# Steering_Daughterboard.net
KiCad netlist of a schematic drawn in Altium Designer
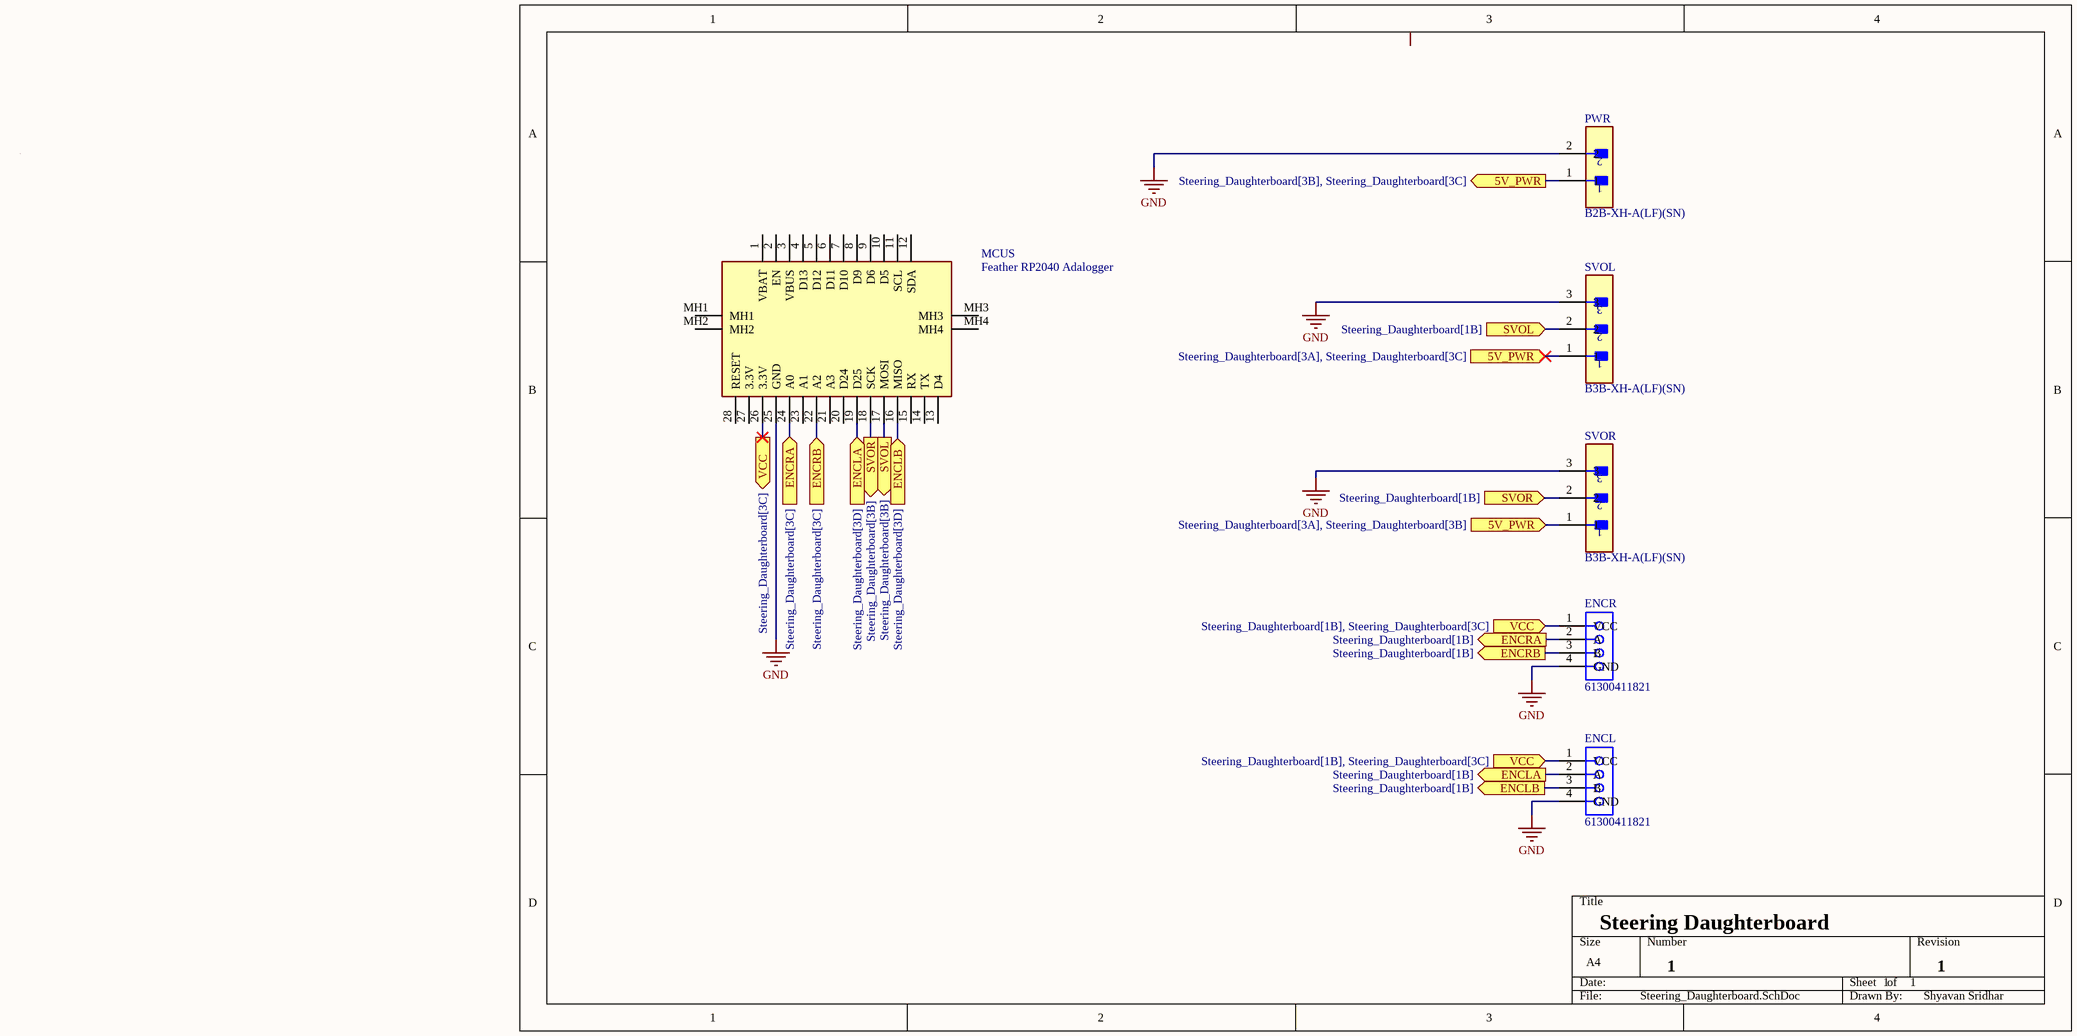
[diagram p0: Steering_Daughterboard.SchDoc]

(export (version "E")
  (design (tool "Eeschema 10.0.6"))
  (components
    (comp (ref "ENCL")
      (value "61300411821")
      (footprint "61300411821")
      (libsource (lib "Altium Content Vault") (part "Header_Female_1R_04P"))
    )
    (comp (ref "ENCR")
      (value "61300411821")
      (footprint "61300411821")
      (libsource (lib "Altium Content Vault") (part "Header_Female_1R_04P"))
    )
    (comp (ref "MCUS")
      (value "Feather RP2040 Adalogger")
      (footprint "SamacSys:2796")
      (description "Adafruit Microcontroller")
      (fields (field (name "MANUFACTURER_PART_NUMBER") "4884") (field (name "MOUSER PART NUMBER") "485-5980"))
      (libsource (lib "*") (part "2796"))
    )
    (comp (ref "PWR")
      (value "B2B-XH-A(LF)(SN)")
      (footprint "FP-B2B-XH-A_LF_SN-MFG")
      (description "CONN HEADER VERT 2POS 2.5MM")
      (libsource (lib "Altium Content Vault") (part "3bc925449376181038e59eaffc5286c"))
    )
    (comp (ref "SVOL")
      (value "B3B-XH-A(LF)(SN)")
      (footprint "FP-B3B-XH-A_LF_SN-MFG")
      (description "CONN HEADER VERT 3POS 2.5MM")
      (libsource (lib "Altium Content Vault") (part "0d3f023dd272f625e17a2be33dea85f"))
    )
    (comp (ref "SVOR")
      (value "B3B-XH-A(LF)(SN)")
      (footprint "FP-B3B-XH-A_LF_SN-MFG")
      (description "CONN HEADER VERT 3POS 2.5MM")
      (libsource (lib "Altium Content Vault") (part "0d3f023dd272f625e17a2be33dea85f"))
    )
  )
  (nets
    (net (code "1") (name "/5V_PWR") (class "Default")
      (node (ref "PWR") (pin "1") (pinfunction "1_1") (pintype "passive"))
      (node (ref "SVOL") (pin "1") (pinfunction "1_1") (pintype "passive"))
      (node (ref "SVOR") (pin "1") (pinfunction "1_1") (pintype "passive"))
    )
    (net (code "2") (name "/ENCLA") (class "Default")
      (node (ref "ENCL") (pin "2") (pinfunction "A_2") (pintype "passive"))
      (node (ref "MCUS") (pin "19") (pinfunction "D25_19") (pintype "passive"))
    )
    (net (code "3") (name "/ENCLB") (class "Default")
      (node (ref "ENCL") (pin "3") (pinfunction "B_3") (pintype "passive"))
      (node (ref "MCUS") (pin "16") (pinfunction "MISO_16") (pintype "passive"))
    )
    (net (code "4") (name "/ENCRA") (class "Default")
      (node (ref "ENCR") (pin "2") (pinfunction "A_2") (pintype "passive"))
      (node (ref "MCUS") (pin "24") (pinfunction "A0_24") (pintype "passive"))
    )
    (net (code "5") (name "/ENCRB") (class "Default")
      (node (ref "ENCR") (pin "3") (pinfunction "B_3") (pintype "passive"))
      (node (ref "MCUS") (pin "22") (pinfunction "A2_22") (pintype "passive"))
    )
    (net (code "6") (name "/SVOL") (class "Default")
      (node (ref "MCUS") (pin "17") (pinfunction "MOSI_17") (pintype "passive"))
      (node (ref "SVOL") (pin "2") (pinfunction "2_2") (pintype "passive"))
    )
    (net (code "7") (name "/SVOR") (class "Default")
      (node (ref "MCUS") (pin "18") (pinfunction "SCK_18") (pintype "passive"))
      (node (ref "SVOR") (pin "2") (pinfunction "2_2") (pintype "passive"))
    )
    (net (code "8") (name "/VCC") (class "Default")
      (node (ref "ENCL") (pin "1") (pinfunction "VCC_1") (pintype "passive"))
      (node (ref "ENCR") (pin "1") (pinfunction "VCC_1") (pintype "passive"))
      (node (ref "MCUS") (pin "26") (pinfunction "3.3V_26") (pintype "passive"))
    )
    (net (code "9") (name "GND") (class "Default")
      (node (ref "ENCL") (pin "4") (pinfunction "GND_4") (pintype "passive"))
      (node (ref "ENCR") (pin "4") (pinfunction "GND_4") (pintype "passive"))
      (node (ref "MCUS") (pin "25") (pinfunction "GND_25") (pintype "passive"))
      (node (ref "PWR") (pin "2") (pinfunction "2_2") (pintype "passive"))
      (node (ref "SVOL") (pin "3") (pinfunction "3_3") (pintype "passive"))
      (node (ref "SVOR") (pin "3") (pinfunction "3_3") (pintype "passive"))
    )
    (net (code "10") (name "unconnected-(MCUS-3.3V-Pad27)") (class "Default")
      (node (ref "MCUS") (pin "27") (pinfunction "3.3V_27") (pintype "passive"))
    )
    (net (code "11") (name "unconnected-(MCUS-A1-Pad23)") (class "Default")
      (node (ref "MCUS") (pin "23") (pinfunction "A1_23") (pintype "passive"))
    )
    (net (code "12") (name "unconnected-(MCUS-A3-Pad21)") (class "Default")
      (node (ref "MCUS") (pin "21") (pinfunction "A3_21") (pintype "passive"))
    )
    (net (code "13") (name "unconnected-(MCUS-D4-Pad13)") (class "Default")
      (node (ref "MCUS") (pin "13") (pinfunction "D4_13") (pintype "passive"))
    )
    (net (code "14") (name "unconnected-(MCUS-D5-Pad10)") (class "Default")
      (node (ref "MCUS") (pin "10") (pinfunction "D5_10") (pintype "passive"))
    )
    (net (code "15") (name "unconnected-(MCUS-D6-Pad9)") (class "Default")
      (node (ref "MCUS") (pin "9") (pinfunction "D6_9") (pintype "passive"))
    )
    (net (code "16") (name "unconnected-(MCUS-D9-Pad8)") (class "Default")
      (node (ref "MCUS") (pin "8") (pinfunction "D9_8") (pintype "passive"))
    )
    (net (code "17") (name "unconnected-(MCUS-D10-Pad7)") (class "Default")
      (node (ref "MCUS") (pin "7") (pinfunction "D10_7") (pintype "passive"))
    )
    (net (code "18") (name "unconnected-(MCUS-D11-Pad6)") (class "Default")
      (node (ref "MCUS") (pin "6") (pinfunction "D11_6") (pintype "passive"))
    )
    (net (code "19") (name "unconnected-(MCUS-D12-Pad5)") (class "Default")
      (node (ref "MCUS") (pin "5") (pinfunction "D12_5") (pintype "passive"))
    )
    (net (code "20") (name "unconnected-(MCUS-D13-Pad4)") (class "Default")
      (node (ref "MCUS") (pin "4") (pinfunction "D13_4") (pintype "passive"))
    )
    (net (code "21") (name "unconnected-(MCUS-D24-Pad20)") (class "Default")
      (node (ref "MCUS") (pin "20") (pinfunction "D24_20") (pintype "passive"))
    )
    (net (code "22") (name "unconnected-(MCUS-EN-Pad2)") (class "Default")
      (node (ref "MCUS") (pin "2") (pinfunction "EN_2") (pintype "passive"))
    )
    (net (code "23") (name "unconnected-(MCUS-PadMH1)") (class "Default")
      (node (ref "MCUS") (pin "MH1") (pinfunction "MH1_MH1") (pintype "passive"))
    )
    (net (code "24") (name "unconnected-(MCUS-PadMH2)") (class "Default")
      (node (ref "MCUS") (pin "MH2") (pinfunction "MH2_MH2") (pintype "passive"))
    )
    (net (code "25") (name "unconnected-(MCUS-PadMH3)") (class "Default")
      (node (ref "MCUS") (pin "MH3") (pinfunction "MH3_MH3") (pintype "passive"))
    )
    (net (code "26") (name "unconnected-(MCUS-PadMH4)") (class "Default")
      (node (ref "MCUS") (pin "MH4") (pinfunction "MH4_MH4") (pintype "passive"))
    )
    (net (code "27") (name "unconnected-(MCUS-RESET-Pad28)") (class "Default")
      (node (ref "MCUS") (pin "28") (pinfunction "RESET_28") (pintype "passive"))
    )
    (net (code "28") (name "unconnected-(MCUS-RX-Pad15)") (class "Default")
      (node (ref "MCUS") (pin "15") (pinfunction "RX_15") (pintype "passive"))
    )
    (net (code "29") (name "unconnected-(MCUS-SCL-Pad11)") (class "Default")
      (node (ref "MCUS") (pin "11") (pinfunction "SCL_11") (pintype "passive"))
    )
    (net (code "30") (name "unconnected-(MCUS-SDA-Pad12)") (class "Default")
      (node (ref "MCUS") (pin "12") (pinfunction "SDA_12") (pintype "passive"))
    )
    (net (code "31") (name "unconnected-(MCUS-TX-Pad14)") (class "Default")
      (node (ref "MCUS") (pin "14") (pinfunction "TX_14") (pintype "passive"))
    )
    (net (code "32") (name "unconnected-(MCUS-VBAT-Pad1)") (class "Default")
      (node (ref "MCUS") (pin "1") (pinfunction "VBAT_1") (pintype "passive"))
    )
    (net (code "33") (name "unconnected-(MCUS-VBUS-Pad3)") (class "Default")
      (node (ref "MCUS") (pin "3") (pinfunction "VBUS_3") (pintype "passive"))
    )
  )
)
